# 12-digit-display.net
KiCad netlist of a schematic drawn in Altium Designer
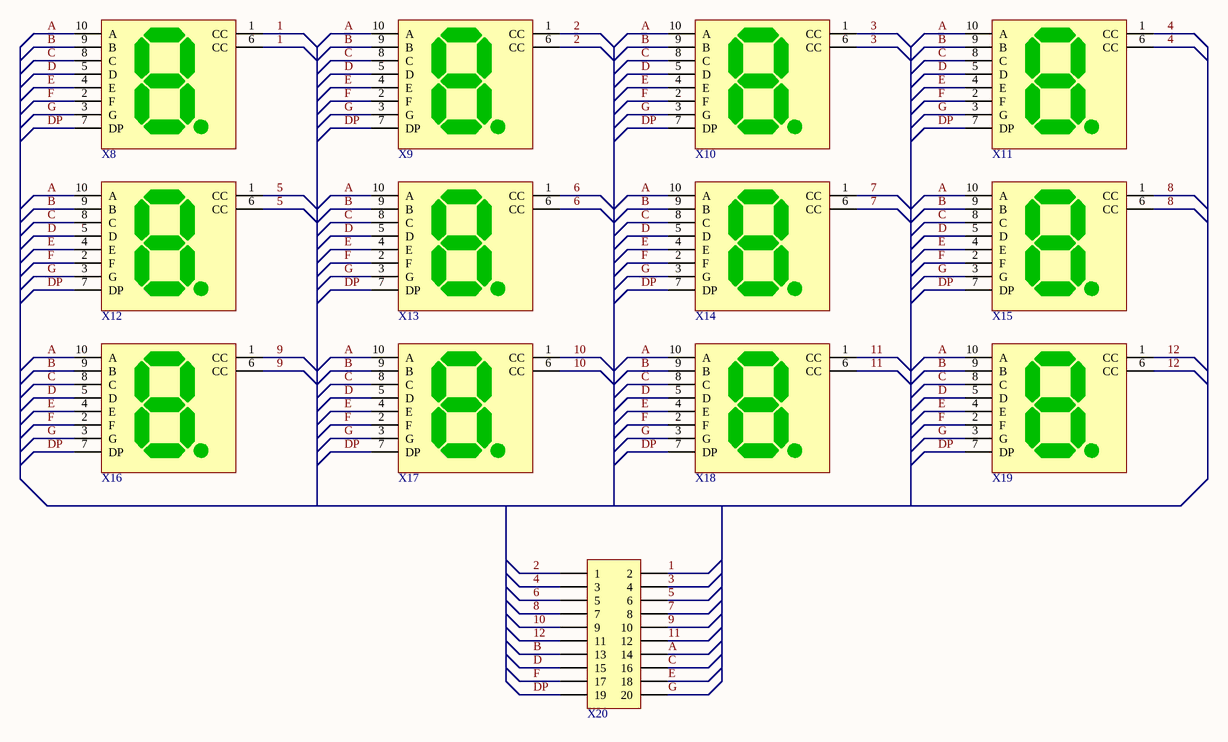
[diagram p0: 12-digit-display.SchDoc]

(export (version "E")
  (design (tool "Eeschema 10.0.6"))
  (components
    (comp (ref "X8") (value "FYS-3912") (footprint "FYS-3916") (libsource (lib "SchLib1") (part "FYS-3912")))
    (comp (ref "X9") (value "FYS-3912") (footprint "FYS-3916") (libsource (lib "SchLib1") (part "FYS-3912")))
    (comp (ref "X10") (value "FYS-3912") (footprint "FYS-3916") (libsource (lib "SchLib1") (part "FYS-3912")))
    (comp (ref "X11") (value "FYS-3912") (footprint "FYS-3916") (libsource (lib "SchLib1") (part "FYS-3912")))
    (comp (ref "X12") (value "FYS-3912") (footprint "FYS-3916") (libsource (lib "SchLib1") (part "FYS-3912")))
    (comp (ref "X13") (value "FYS-3912") (footprint "FYS-3916") (libsource (lib "SchLib1") (part "FYS-3912")))
    (comp (ref "X14") (value "FYS-3912") (footprint "FYS-3916") (libsource (lib "SchLib1") (part "FYS-3912")))
    (comp (ref "X15") (value "FYS-3912") (footprint "FYS-3916") (libsource (lib "SchLib1") (part "FYS-3912")))
    (comp (ref "X16") (value "FYS-3912") (footprint "FYS-3916") (libsource (lib "SchLib1") (part "FYS-3912")))
    (comp (ref "X17") (value "FYS-3912") (footprint "FYS-3916") (libsource (lib "SchLib1") (part "FYS-3912")))
    (comp (ref "X18") (value "FYS-3912") (footprint "FYS-3916") (libsource (lib "SchLib1") (part "FYS-3912")))
    (comp (ref "X19") (value "FYS-3912") (footprint "FYS-3916") (libsource (lib "SchLib1") (part "FYS-3912")))
    (comp (ref "X20")
      (value "DIL-CONN-20")
      (footprint "DIL-CONN-IDC-20R")
      (libsource (lib "SchLib1") (part "DIL-CONN-20"))
    )
  )
  (nets
    (net (code "1") (name "/1") (class "Default")
      (node (ref "X20") (pin "2") (pinfunction "2_2") (pintype "passive"))
      (node (ref "X8") (pin "1") (pinfunction "CC_1") (pintype "passive"))
      (node (ref "X8") (pin "6") (pinfunction "CC_6") (pintype "passive"))
    )
    (net (code "2") (name "/2") (class "Default")
      (node (ref "X20") (pin "1") (pinfunction "1_1") (pintype "passive"))
      (node (ref "X9") (pin "1") (pinfunction "CC_1") (pintype "passive"))
      (node (ref "X9") (pin "6") (pinfunction "CC_6") (pintype "passive"))
    )
    (net (code "3") (name "/3") (class "Default")
      (node (ref "X10") (pin "1") (pinfunction "CC_1") (pintype "passive"))
      (node (ref "X10") (pin "6") (pinfunction "CC_6") (pintype "passive"))
      (node (ref "X20") (pin "4") (pinfunction "4_4") (pintype "passive"))
    )
    (net (code "4") (name "/4") (class "Default")
      (node (ref "X11") (pin "1") (pinfunction "CC_1") (pintype "passive"))
      (node (ref "X11") (pin "6") (pinfunction "CC_6") (pintype "passive"))
      (node (ref "X20") (pin "3") (pinfunction "3_3") (pintype "passive"))
    )
    (net (code "5") (name "/5") (class "Default")
      (node (ref "X12") (pin "1") (pinfunction "CC_1") (pintype "passive"))
      (node (ref "X12") (pin "6") (pinfunction "CC_6") (pintype "passive"))
      (node (ref "X20") (pin "6") (pinfunction "6_6") (pintype "passive"))
    )
    (net (code "6") (name "/6") (class "Default")
      (node (ref "X13") (pin "1") (pinfunction "CC_1") (pintype "passive"))
      (node (ref "X13") (pin "6") (pinfunction "CC_6") (pintype "passive"))
      (node (ref "X20") (pin "5") (pinfunction "5_5") (pintype "passive"))
    )
    (net (code "7") (name "/7") (class "Default")
      (node (ref "X14") (pin "1") (pinfunction "CC_1") (pintype "passive"))
      (node (ref "X14") (pin "6") (pinfunction "CC_6") (pintype "passive"))
      (node (ref "X20") (pin "8") (pinfunction "8_8") (pintype "passive"))
    )
    (net (code "8") (name "/8") (class "Default")
      (node (ref "X15") (pin "1") (pinfunction "CC_1") (pintype "passive"))
      (node (ref "X15") (pin "6") (pinfunction "CC_6") (pintype "passive"))
      (node (ref "X20") (pin "7") (pinfunction "7_7") (pintype "passive"))
    )
    (net (code "9") (name "/9") (class "Default")
      (node (ref "X16") (pin "1") (pinfunction "CC_1") (pintype "passive"))
      (node (ref "X16") (pin "6") (pinfunction "CC_6") (pintype "passive"))
      (node (ref "X20") (pin "10") (pinfunction "10_10") (pintype "passive"))
    )
    (net (code "10") (name "/10") (class "Default")
      (node (ref "X17") (pin "1") (pinfunction "CC_1") (pintype "passive"))
      (node (ref "X17") (pin "6") (pinfunction "CC_6") (pintype "passive"))
      (node (ref "X20") (pin "9") (pinfunction "9_9") (pintype "passive"))
    )
    (net (code "11") (name "/11") (class "Default")
      (node (ref "X18") (pin "1") (pinfunction "CC_1") (pintype "passive"))
      (node (ref "X18") (pin "6") (pinfunction "CC_6") (pintype "passive"))
      (node (ref "X20") (pin "12") (pinfunction "12_12") (pintype "passive"))
    )
    (net (code "12") (name "/12") (class "Default")
      (node (ref "X19") (pin "1") (pinfunction "CC_1") (pintype "passive"))
      (node (ref "X19") (pin "6") (pinfunction "CC_6") (pintype "passive"))
      (node (ref "X20") (pin "11") (pinfunction "11_11") (pintype "passive"))
    )
    (net (code "13") (name "/A") (class "Default")
      (node (ref "X10") (pin "10") (pinfunction "A_10") (pintype "passive"))
      (node (ref "X11") (pin "10") (pinfunction "A_10") (pintype "passive"))
      (node (ref "X12") (pin "10") (pinfunction "A_10") (pintype "passive"))
      (node (ref "X13") (pin "10") (pinfunction "A_10") (pintype "passive"))
      (node (ref "X14") (pin "10") (pinfunction "A_10") (pintype "passive"))
      (node (ref "X15") (pin "10") (pinfunction "A_10") (pintype "passive"))
      (node (ref "X16") (pin "10") (pinfunction "A_10") (pintype "passive"))
      (node (ref "X17") (pin "10") (pinfunction "A_10") (pintype "passive"))
      (node (ref "X18") (pin "10") (pinfunction "A_10") (pintype "passive"))
      (node (ref "X19") (pin "10") (pinfunction "A_10") (pintype "passive"))
      (node (ref "X20") (pin "14") (pinfunction "14_14") (pintype "passive"))
      (node (ref "X8") (pin "10") (pinfunction "A_10") (pintype "passive"))
      (node (ref "X9") (pin "10") (pinfunction "A_10") (pintype "passive"))
    )
    (net (code "14") (name "/B") (class "Default")
      (node (ref "X10") (pin "9") (pinfunction "B_9") (pintype "passive"))
      (node (ref "X11") (pin "9") (pinfunction "B_9") (pintype "passive"))
      (node (ref "X12") (pin "9") (pinfunction "B_9") (pintype "passive"))
      (node (ref "X13") (pin "9") (pinfunction "B_9") (pintype "passive"))
      (node (ref "X14") (pin "9") (pinfunction "B_9") (pintype "passive"))
      (node (ref "X15") (pin "9") (pinfunction "B_9") (pintype "passive"))
      (node (ref "X16") (pin "9") (pinfunction "B_9") (pintype "passive"))
      (node (ref "X17") (pin "9") (pinfunction "B_9") (pintype "passive"))
      (node (ref "X18") (pin "9") (pinfunction "B_9") (pintype "passive"))
      (node (ref "X19") (pin "9") (pinfunction "B_9") (pintype "passive"))
      (node (ref "X20") (pin "13") (pinfunction "13_13") (pintype "passive"))
      (node (ref "X8") (pin "9") (pinfunction "B_9") (pintype "passive"))
      (node (ref "X9") (pin "9") (pinfunction "B_9") (pintype "passive"))
    )
    (net (code "15") (name "/C") (class "Default")
      (node (ref "X10") (pin "8") (pinfunction "C_8") (pintype "passive"))
      (node (ref "X11") (pin "8") (pinfunction "C_8") (pintype "passive"))
      (node (ref "X12") (pin "8") (pinfunction "C_8") (pintype "passive"))
      (node (ref "X13") (pin "8") (pinfunction "C_8") (pintype "passive"))
      (node (ref "X14") (pin "8") (pinfunction "C_8") (pintype "passive"))
      (node (ref "X15") (pin "8") (pinfunction "C_8") (pintype "passive"))
      (node (ref "X16") (pin "8") (pinfunction "C_8") (pintype "passive"))
      (node (ref "X17") (pin "8") (pinfunction "C_8") (pintype "passive"))
      (node (ref "X18") (pin "8") (pinfunction "C_8") (pintype "passive"))
      (node (ref "X19") (pin "8") (pinfunction "C_8") (pintype "passive"))
      (node (ref "X20") (pin "16") (pinfunction "16_16") (pintype "passive"))
      (node (ref "X8") (pin "8") (pinfunction "C_8") (pintype "passive"))
      (node (ref "X9") (pin "8") (pinfunction "C_8") (pintype "passive"))
    )
    (net (code "16") (name "/D") (class "Default")
      (node (ref "X10") (pin "5") (pinfunction "D_5") (pintype "passive"))
      (node (ref "X11") (pin "5") (pinfunction "D_5") (pintype "passive"))
      (node (ref "X12") (pin "5") (pinfunction "D_5") (pintype "passive"))
      (node (ref "X13") (pin "5") (pinfunction "D_5") (pintype "passive"))
      (node (ref "X14") (pin "5") (pinfunction "D_5") (pintype "passive"))
      (node (ref "X15") (pin "5") (pinfunction "D_5") (pintype "passive"))
      (node (ref "X16") (pin "5") (pinfunction "D_5") (pintype "passive"))
      (node (ref "X17") (pin "5") (pinfunction "D_5") (pintype "passive"))
      (node (ref "X18") (pin "5") (pinfunction "D_5") (pintype "passive"))
      (node (ref "X19") (pin "5") (pinfunction "D_5") (pintype "passive"))
      (node (ref "X20") (pin "15") (pinfunction "15_15") (pintype "passive"))
      (node (ref "X8") (pin "5") (pinfunction "D_5") (pintype "passive"))
      (node (ref "X9") (pin "5") (pinfunction "D_5") (pintype "passive"))
    )
    (net (code "17") (name "/DP") (class "Default")
      (node (ref "X10") (pin "7") (pinfunction "DP_7") (pintype "passive"))
      (node (ref "X11") (pin "7") (pinfunction "DP_7") (pintype "passive"))
      (node (ref "X12") (pin "7") (pinfunction "DP_7") (pintype "passive"))
      (node (ref "X13") (pin "7") (pinfunction "DP_7") (pintype "passive"))
      (node (ref "X14") (pin "7") (pinfunction "DP_7") (pintype "passive"))
      (node (ref "X15") (pin "7") (pinfunction "DP_7") (pintype "passive"))
      (node (ref "X16") (pin "7") (pinfunction "DP_7") (pintype "passive"))
      (node (ref "X17") (pin "7") (pinfunction "DP_7") (pintype "passive"))
      (node (ref "X18") (pin "7") (pinfunction "DP_7") (pintype "passive"))
      (node (ref "X19") (pin "7") (pinfunction "DP_7") (pintype "passive"))
      (node (ref "X20") (pin "19") (pinfunction "19_19") (pintype "passive"))
      (node (ref "X8") (pin "7") (pinfunction "DP_7") (pintype "passive"))
      (node (ref "X9") (pin "7") (pinfunction "DP_7") (pintype "passive"))
    )
    (net (code "18") (name "/E") (class "Default")
      (node (ref "X10") (pin "4") (pinfunction "E_4") (pintype "passive"))
      (node (ref "X11") (pin "4") (pinfunction "E_4") (pintype "passive"))
      (node (ref "X12") (pin "4") (pinfunction "E_4") (pintype "passive"))
      (node (ref "X13") (pin "4") (pinfunction "E_4") (pintype "passive"))
      (node (ref "X14") (pin "4") (pinfunction "E_4") (pintype "passive"))
      (node (ref "X15") (pin "4") (pinfunction "E_4") (pintype "passive"))
      (node (ref "X16") (pin "4") (pinfunction "E_4") (pintype "passive"))
      (node (ref "X17") (pin "4") (pinfunction "E_4") (pintype "passive"))
      (node (ref "X18") (pin "4") (pinfunction "E_4") (pintype "passive"))
      (node (ref "X19") (pin "4") (pinfunction "E_4") (pintype "passive"))
      (node (ref "X20") (pin "18") (pinfunction "18_18") (pintype "passive"))
      (node (ref "X8") (pin "4") (pinfunction "E_4") (pintype "passive"))
      (node (ref "X9") (pin "4") (pinfunction "E_4") (pintype "passive"))
    )
    (net (code "19") (name "/F") (class "Default")
      (node (ref "X10") (pin "2") (pinfunction "F_2") (pintype "passive"))
      (node (ref "X11") (pin "2") (pinfunction "F_2") (pintype "passive"))
      (node (ref "X12") (pin "2") (pinfunction "F_2") (pintype "passive"))
      (node (ref "X13") (pin "2") (pinfunction "F_2") (pintype "passive"))
      (node (ref "X14") (pin "2") (pinfunction "F_2") (pintype "passive"))
      (node (ref "X15") (pin "2") (pinfunction "F_2") (pintype "passive"))
      (node (ref "X16") (pin "2") (pinfunction "F_2") (pintype "passive"))
      (node (ref "X17") (pin "2") (pinfunction "F_2") (pintype "passive"))
      (node (ref "X18") (pin "2") (pinfunction "F_2") (pintype "passive"))
      (node (ref "X19") (pin "2") (pinfunction "F_2") (pintype "passive"))
      (node (ref "X20") (pin "17") (pinfunction "17_17") (pintype "passive"))
      (node (ref "X8") (pin "2") (pinfunction "F_2") (pintype "passive"))
      (node (ref "X9") (pin "2") (pinfunction "F_2") (pintype "passive"))
    )
    (net (code "20") (name "/G") (class "Default")
      (node (ref "X10") (pin "3") (pinfunction "G_3") (pintype "passive"))
      (node (ref "X11") (pin "3") (pinfunction "G_3") (pintype "passive"))
      (node (ref "X12") (pin "3") (pinfunction "G_3") (pintype "passive"))
      (node (ref "X13") (pin "3") (pinfunction "G_3") (pintype "passive"))
      (node (ref "X14") (pin "3") (pinfunction "G_3") (pintype "passive"))
      (node (ref "X15") (pin "3") (pinfunction "G_3") (pintype "passive"))
      (node (ref "X16") (pin "3") (pinfunction "G_3") (pintype "passive"))
      (node (ref "X17") (pin "3") (pinfunction "G_3") (pintype "passive"))
      (node (ref "X18") (pin "3") (pinfunction "G_3") (pintype "passive"))
      (node (ref "X19") (pin "3") (pinfunction "G_3") (pintype "passive"))
      (node (ref "X20") (pin "20") (pinfunction "20_20") (pintype "passive"))
      (node (ref "X8") (pin "3") (pinfunction "G_3") (pintype "passive"))
      (node (ref "X9") (pin "3") (pinfunction "G_3") (pintype "passive"))
    )
  )
)
